# business_card.net
KiCad netlist of a schematic drawn in EAGLE
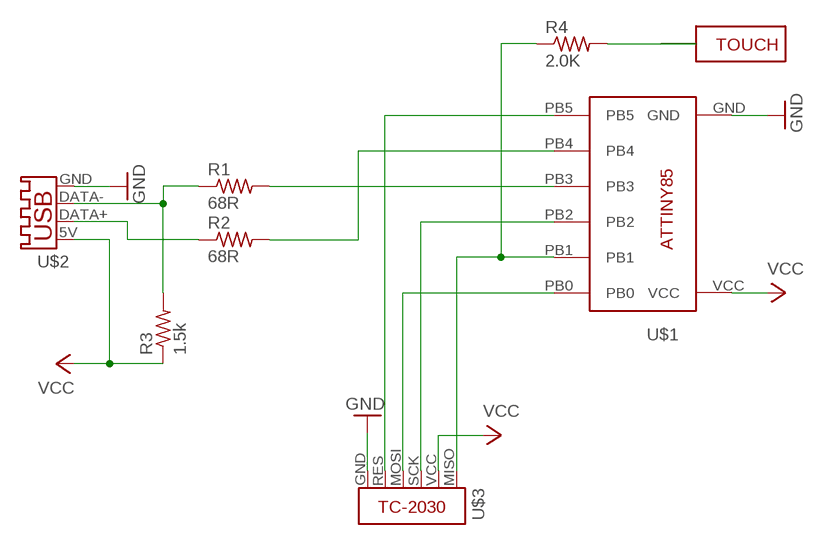
[diagram p0: schematic, sheet 1]

(export (version "E")
  (design (tool "Eeschema 10.0.6"))
  (components
    (comp (ref "R1")
      (value "68R")
      (footprint "eagle-import:0805")
      (libsource (lib "eagle-import") (part "0805_RESISTOR"))
    )
    (comp (ref "R2")
      (value "68R")
      (footprint "eagle-import:0805")
      (libsource (lib "eagle-import") (part "0805_RESISTOR"))
    )
    (comp (ref "R3")
      (value "1.5k")
      (footprint "eagle-import:0805")
      (libsource (lib "eagle-import") (part "0805_RESISTOR"))
    )
    (comp (ref "R4")
      (value "2.0K")
      (footprint "eagle-import:0603")
      (libsource (lib "eagle-import") (part "0603_RESISTOR"))
    )
    (comp (ref "U$1")
      (value "ATTINY85-20SU")
      (footprint "eagle-import:8SU")
      (libsource (lib "eagle-import") (part "ATTINY85-20SU"))
    )
    (comp (ref "U$2")
      (value "USB_MALE")
      (footprint "eagle-import:USB_MALE")
      (libsource (lib "eagle-import") (part "USB_MALE"))
    )
    (comp (ref "U$3")
      (value "TAG_CONNECT_TC2030")
      (footprint "eagle-import:TC2030-IDC-NL")
      (libsource (lib "eagle-import") (part "TAG_CONNECT_TC2030"))
    )
    (comp (ref "U$4")
      (value "TOUCH_PAD")
      (footprint "eagle-import:SQUARE_PAD")
      (libsource (lib "eagle-import") (part "TOUCH_PAD"))
    )
  )
  (nets
    (net (code "1") (name "GND") (class "Default")
      (node (ref "U$1") (pin "GND") (pinfunction "GND_GND") (pintype "bidirectional"))
      (node (ref "U$2") (pin "GND") (pinfunction "GND_GND") (pintype "passive"))
      (node (ref "U$3") (pin "GND") (pinfunction "GND_GND") (pintype "bidirectional"))
    )
    (net (code "2") (name "Net-(R1-1)") (class "Default")
      (node (ref "R1") (pin "P$1") (pinfunction "1_P$1") (pintype "passive"))
      (node (ref "R3") (pin "P$2") (pinfunction "2_P$2") (pintype "passive"))
      (node (ref "U$2") (pin "DATA-") (pinfunction "D-_DATA-") (pintype "passive"))
    )
    (net (code "3") (name "Net-(R1-2)") (class "Default")
      (node (ref "R1") (pin "P$2") (pinfunction "2_P$2") (pintype "passive"))
      (node (ref "U$1") (pin "PB3") (pinfunction "PB3_PB3") (pintype "bidirectional"))
    )
    (net (code "4") (name "Net-(R2-1)") (class "Default")
      (node (ref "R2") (pin "P$1") (pinfunction "1_P$1") (pintype "passive"))
      (node (ref "U$2") (pin "DATA+") (pinfunction "D+_DATA+") (pintype "passive"))
    )
    (net (code "5") (name "Net-(R2-2)") (class "Default")
      (node (ref "R2") (pin "P$2") (pinfunction "2_P$2") (pintype "passive"))
      (node (ref "U$1") (pin "PB4") (pinfunction "PB4_PB4") (pintype "bidirectional"))
    )
    (net (code "6") (name "Net-(R4-1)") (class "Default")
      (node (ref "R4") (pin "IN") (pinfunction "1_IN") (pintype "passive"))
      (node (ref "U$1") (pin "PB1") (pinfunction "PB1_PB1") (pintype "bidirectional"))
      (node (ref "U$3") (pin "MISO") (pinfunction "MISO_MISO") (pintype "bidirectional"))
    )
    (net (code "7") (name "Net-(R4-2)") (class "Default")
      (node (ref "R4") (pin "OUT") (pinfunction "2_OUT") (pintype "passive"))
      (node (ref "U$4") (pin "P$1") (pinfunction "P$1_P$1") (pintype "bidirectional"))
    )
    (net (code "8") (name "Net-(U$1-PadPB0)") (class "Default")
      (node (ref "U$1") (pin "PB0") (pinfunction "PB0_PB0") (pintype "bidirectional"))
      (node (ref "U$3") (pin "MOSI") (pinfunction "MOSI_MOSI") (pintype "bidirectional"))
    )
    (net (code "9") (name "Net-(U$1-PadPB2)") (class "Default")
      (node (ref "U$1") (pin "PB2") (pinfunction "PB2_PB2") (pintype "bidirectional"))
      (node (ref "U$3") (pin "SCK") (pinfunction "SCK_SCK") (pintype "bidirectional"))
    )
    (net (code "10") (name "Net-(U$3-RESET)") (class "Default")
      (node (ref "U$1") (pin "PB5") (pinfunction "PB5_PB5") (pintype "bidirectional"))
      (node (ref "U$3") (pin "RES") (pinfunction "RESET_RES") (pintype "bidirectional"))
    )
    (net (code "11") (name "VCC") (class "Default")
      (node (ref "R3") (pin "P$1") (pinfunction "1_P$1") (pintype "passive"))
      (node (ref "U$1") (pin "VCC") (pinfunction "VCC_VCC") (pintype "bidirectional"))
      (node (ref "U$2") (pin "5V") (pinfunction "VCC_5V") (pintype "passive"))
      (node (ref "U$3") (pin "VCC") (pinfunction "VCC_VCC") (pintype "bidirectional"))
    )
  )
)
